# EEM_Connectors.net
KiCad netlist of a schematic drawn in Altium Designer
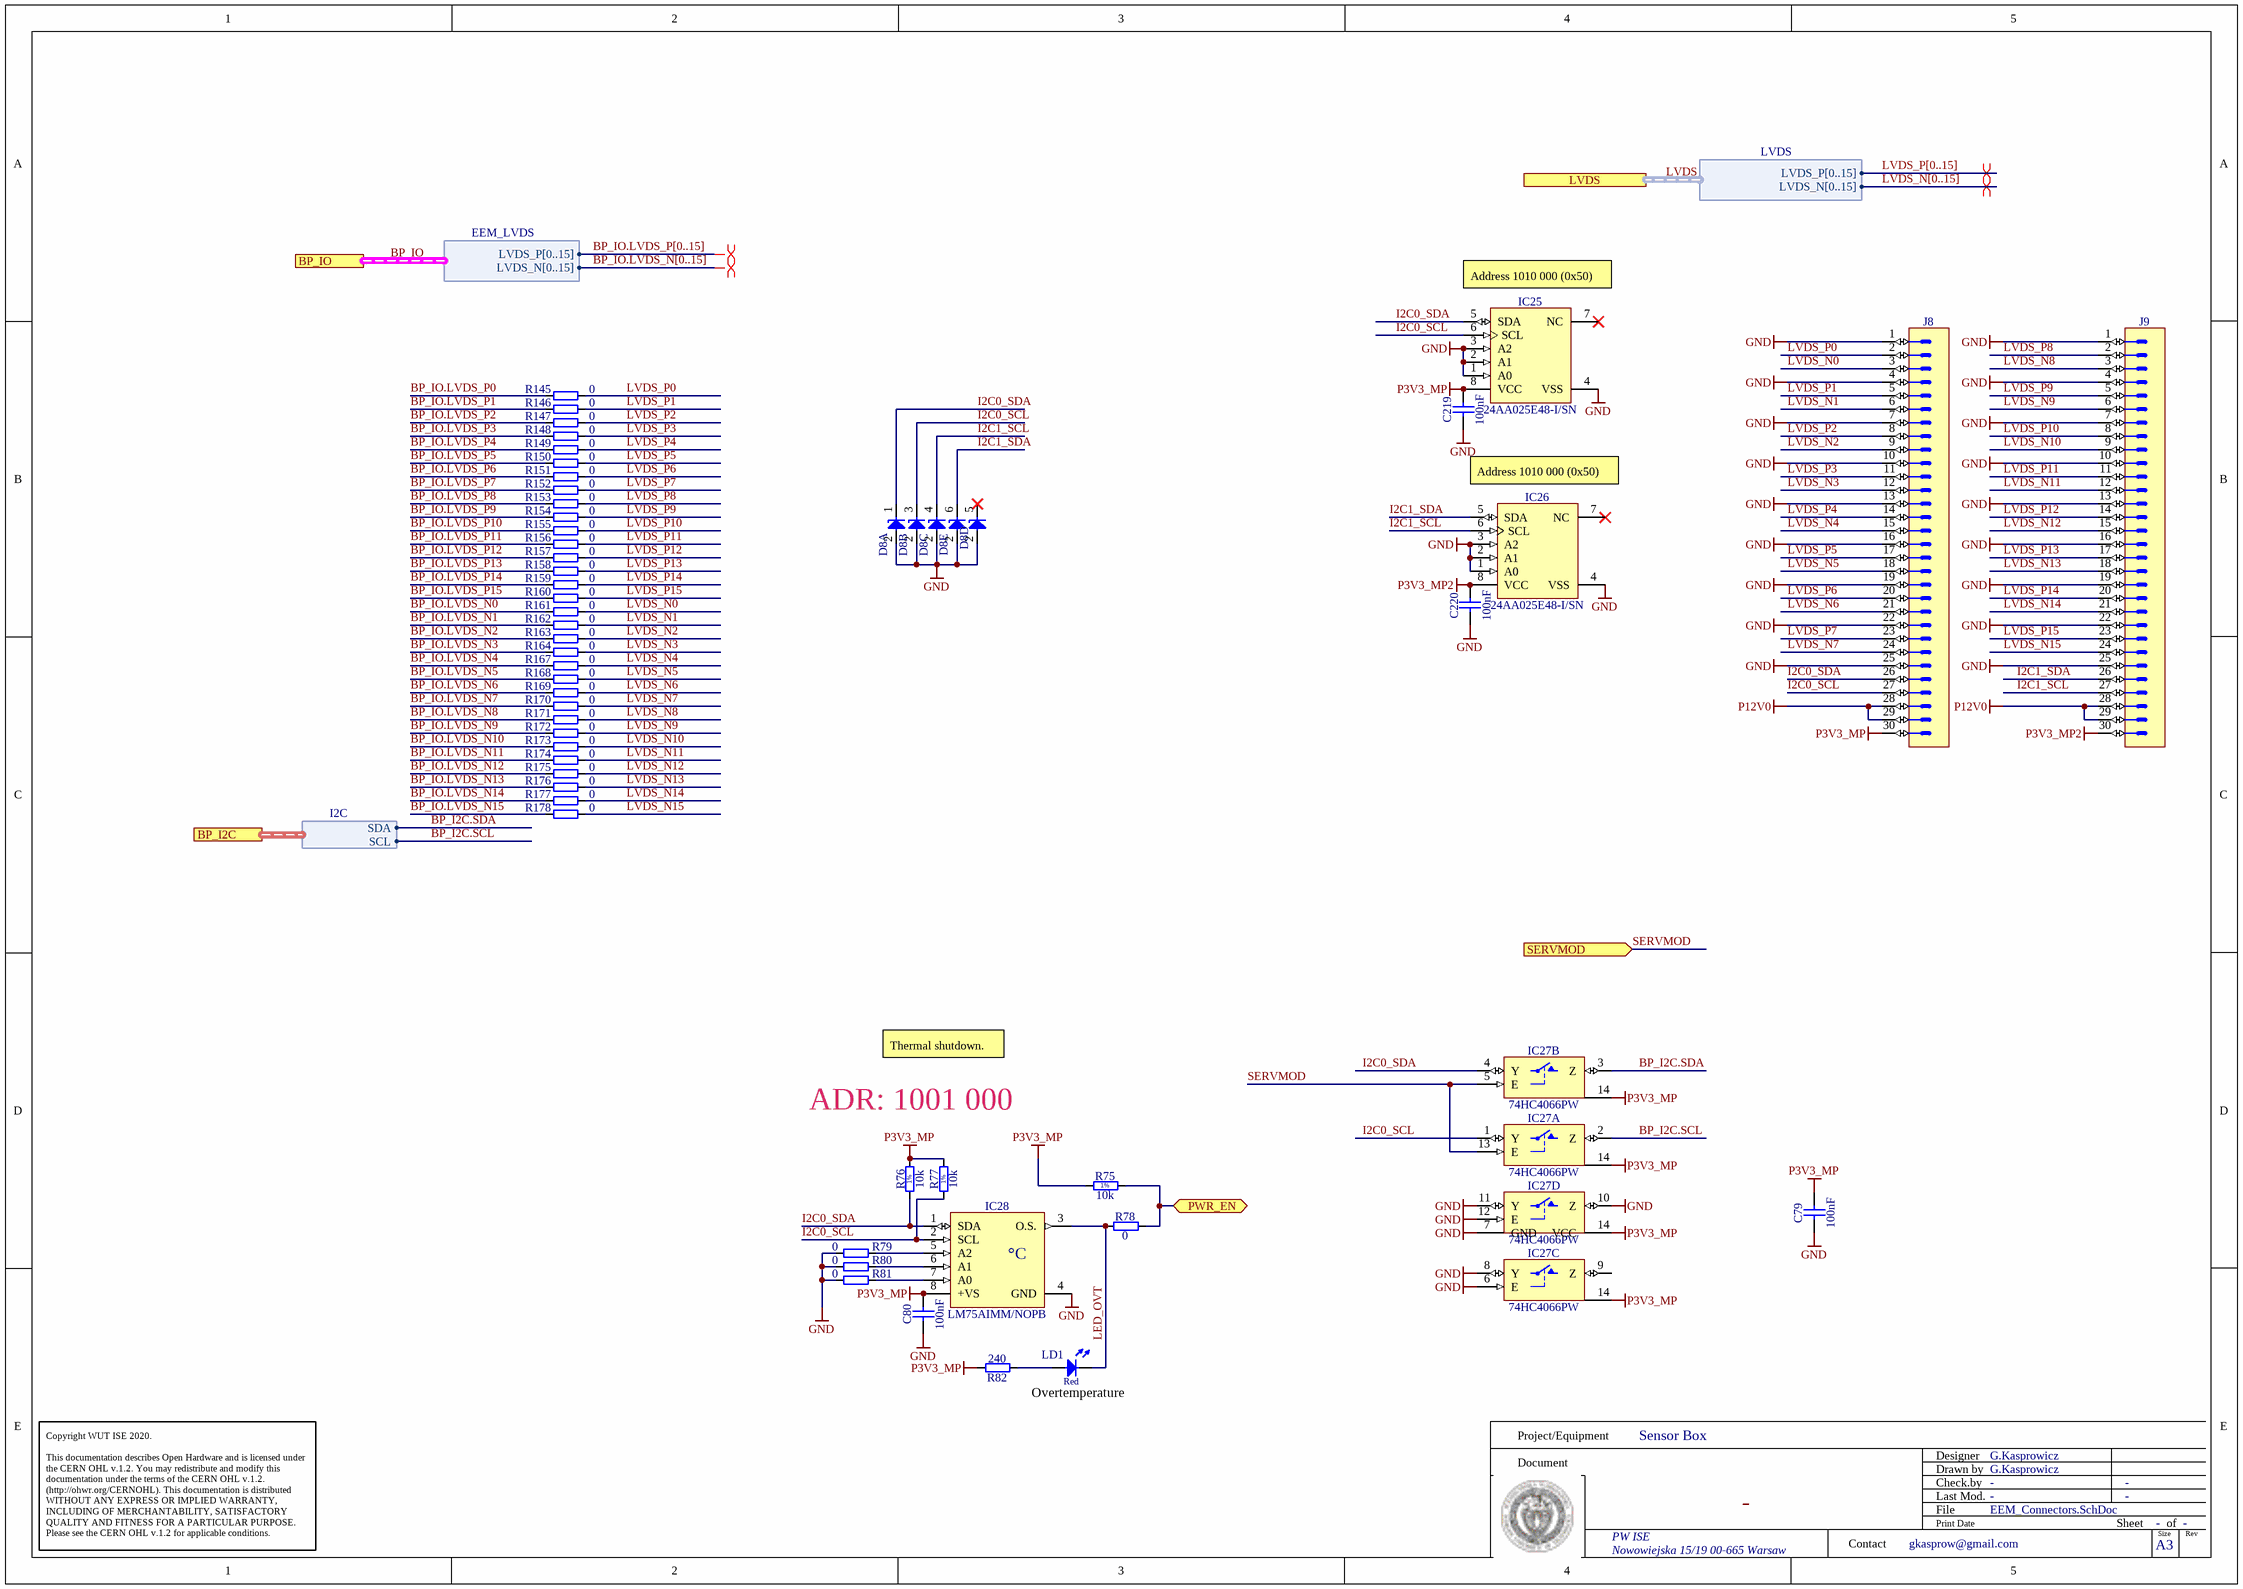
[diagram p0: EEM_Connectors.SchDoc]

(export (version "E")
  (design (tool "Eeschema 10.0.6"))
  (components
    (comp (ref "C79")
      (value "100nF")
      (footprint "CAPC1005X55N")
      (description "Non-polarised capacitor")
      (fields
        (field (name "PART NUMBER") "CC0402_100NF_16V_10%_X5R")
        (field (name "VOLTAGE") "16V")
        (field (name "AUTHOR") "CERN DEM JLC")
      )
      (libsource (lib "Capacitors") (part "Capacitor - non polarized"))
    )
    (comp (ref "C80")
      (value "100nF")
      (footprint "CAPC1005X55N")
      (description "Non-polarised capacitor")
      (fields
        (field (name "PART NUMBER") "CC0402_100NF_16V_10%_X5R")
        (field (name "VOLTAGE") "16V")
        (field (name "AUTHOR") "CERN DEM JLC")
      )
      (libsource (lib "Capacitors") (part "Capacitor - non polarized"))
    )
    (comp (ref "C219")
      (value "100nF")
      (footprint "CAPC1005X55N")
      (description "Non-polarised capacitor")
      (fields
        (field (name "PART NUMBER") "CC0402_100NF_16V_10%_X5R")
        (field (name "VOLTAGE") "16V")
        (field (name "AUTHOR") "CERN DEM JLC")
      )
      (libsource (lib "Capacitors") (part "Capacitor - non polarized"))
    )
    (comp (ref "C220")
      (value "100nF")
      (footprint "CAPC1005X55N")
      (description "Non-polarised capacitor")
      (fields
        (field (name "PART NUMBER") "CC0402_100NF_16V_10%_X5R")
        (field (name "VOLTAGE") "16V")
        (field (name "AUTHOR") "CERN DEM JLC")
      )
      (libsource (lib "Capacitors") (part "Capacitor - non polarized"))
    )
    (comp (ref "D8")
      (value "PESD3V3L5UY")
      (footprint "SOT65P210X110-6N")
      (description "Fivefold ESD Protection Diode Arrays")
      (fields
        (field (name "VOLTAGE") "3.3V")
        (field (name "POWER") "200W")
        (field (name "AUTHOR") "CERN DEM WB")
      )
      (libsource (lib "ICs And Semiconductors") (part "PESD Array 5diodes 6pins Common anode2"))
    )
    (comp (ref "IC25")
      (value "24AA025E48-I/SN")
      (footprint "SOIC127P600X175-8N")
      (description "1.7V-5.5V, 2K I2C™ Serial EEPROMs with EUI-48™ Node Identity")
      (fields (field (name "MANUFACTURER") "MICROCHIP TECHNOLOGY") (field (name "AUTHOR") "CERN DEM MR"))
      (libsource (lib "ICs And Semiconductors") (part "24AA025E48-I/SN"))
    )
    (comp (ref "IC26")
      (value "24AA025E48-I/SN")
      (footprint "SOIC127P600X175-8N")
      (description "1.7V-5.5V, 2K I2C™ Serial EEPROMs with EUI-48™ Node Identity")
      (fields (field (name "MANUFACTURER") "MICROCHIP TECHNOLOGY") (field (name "AUTHOR") "CERN DEM MR"))
      (libsource (lib "ICs And Semiconductors") (part "24AA025E48-I/SN"))
    )
    (comp (ref "IC27")
      (value "74HC4066PW")
      (footprint "SOP65P640X110-14N")
      (fields (field (name "MANUFACTURER") "NXP SEMICONDUCTORS") (field (name "AUTHOR") "CERN DEM JLC"))
      (libsource (lib "ICs And Semiconductors") (part "4066"))
    )
    (comp (ref "IC28")
      (value "LM75AIMM/NOPB")
      (footprint "SOP65P490X109-8N")
      (description "Digital Temperature Sensor and Thermal Watchdog with Two-Wire Interface")
      (fields (field (name "MANUFACTURER") "TEXAS INSTRUMENTS") (field (name "AUTHOR") "CERN DEM JLC"))
      (libsource (lib "ICs And Semiconductors") (part "LM75"))
    )
    (comp (ref "J8")
      (value "~")
      (footprint "3M_N2530-6002RB")
      (description "Connector 30 Male")
      (fields
        (field (name "PART NUMBER") "3M_N2530-6002RB")
        (field (name "MANUFACTURER") "3M")
        (field (name "AUTHOR") "CERN DEM JLC")
      )
      (libsource (lib "Connectors") (part "Connector 30 Male"))
    )
    (comp (ref "J9")
      (value "~")
      (footprint "3M_N2530-6002RB")
      (description "Connector 30 Male")
      (fields
        (field (name "PART NUMBER") "3M_N2530-6002RB")
        (field (name "MANUFACTURER") "3M")
        (field (name "AUTHOR") "CERN DEM JLC")
      )
      (libsource (lib "Connectors") (part "Connector 30 Male"))
    )
    (comp (ref "LD1")
      (value "Red")
      (footprint "LED_AVAGO_HSMC-C120")
      (description "LED Red 1C 2A")
      (fields
        (field (name "PART NUMBER") "LED_AVAGO_HSMC-C120")
        (field (name "MANUFACTURER") "AVAGO TECHNOLOGIES")
        (field (name "AUTHOR") "CERN DEM JMW")
      )
      (libsource (lib "ICs And Semiconductors") (part "LED Red 1C 2A"))
    )
    (comp (ref "R75")
      (value "10k")
      (footprint "RESC1005X40N")
      (description "Resistor - 1%")
      (fields
        (field (name "PART NUMBER") "R0402_10K_1%_0.0625W_100PPM")
        (field (name "POWER") "0.0625W")
        (field (name "AUTHOR") "CERN DEM JLC")
      )
      (libsource (lib "Resistors") (part "Resistor - 1%"))
    )
    (comp (ref "R76")
      (value "10k")
      (footprint "RESC1005X40N")
      (description "Resistor - 1%")
      (fields
        (field (name "PART NUMBER") "R0402_10K_1%_0.0625W_100PPM")
        (field (name "POWER") "0.0625W")
        (field (name "AUTHOR") "CERN DEM JLC")
      )
      (libsource (lib "Resistors") (part "Resistor - 1%"))
    )
    (comp (ref "R77")
      (value "10k")
      (footprint "RESC1005X40N")
      (description "Resistor - 1%")
      (fields
        (field (name "PART NUMBER") "R0402_10K_1%_0.0625W_100PPM")
        (field (name "POWER") "0.0625W")
        (field (name "AUTHOR") "CERN DEM JLC")
      )
      (libsource (lib "Resistors") (part "Resistor - 1%"))
    )
    (comp (ref "R78")
      (value "0")
      (footprint "RESC1005X40N")
      (description "Resistor")
      (fields
        (field (name "PART NUMBER") "R0402_0R_JUMPER")
        (field (name "MANUFACTURER") "GENERIC")
        (field (name "AUTHOR") "CERN DEM JLC")
      )
      (libsource (lib "Resistors") (part "Resistor"))
    )
    (comp (ref "R79")
      (value "0")
      (footprint "RESC1005X40N")
      (description "Resistor")
      (fields
        (field (name "PART NUMBER") "R0402_0R_JUMPER")
        (field (name "MANUFACTURER") "GENERIC")
        (field (name "AUTHOR") "CERN DEM JLC")
      )
      (libsource (lib "Resistors") (part "Resistor"))
    )
    (comp (ref "R80")
      (value "0")
      (footprint "RESC1005X40N")
      (description "Resistor")
      (fields
        (field (name "PART NUMBER") "R0402_0R_JUMPER")
        (field (name "MANUFACTURER") "GENERIC")
        (field (name "AUTHOR") "CERN DEM JLC")
      )
      (libsource (lib "Resistors") (part "Resistor"))
    )
    (comp (ref "R81")
      (value "0")
      (footprint "RESC1005X40N")
      (description "Resistor")
      (fields
        (field (name "PART NUMBER") "R0402_0R_JUMPER")
        (field (name "MANUFACTURER") "GENERIC")
        (field (name "AUTHOR") "CERN DEM JLC")
      )
      (libsource (lib "Resistors") (part "Resistor"))
    )
    (comp (ref "R82")
      (value "240")
      (footprint "RESC1005X40N")
      (description "Resistor - 1%")
      (fields
        (field (name "PART NUMBER") "R0402_240R_1%_0.0625W_100PPM")
        (field (name "POWER") "0.0625W")
        (field (name "AUTHOR") "CERN DEM JLC")
      )
      (libsource (lib "Resistors") (part "Resistor - 1%"))
    )
    (comp (ref "R145")
      (value "0")
      (footprint "RESC1005X40N")
      (description "Resistor")
      (fields
        (field (name "PART NUMBER") "R0402_0R_JUMPER")
        (field (name "MANUFACTURER") "GENERIC")
        (field (name "AUTHOR") "CERN DEM JLC")
      )
      (libsource (lib "Resistors") (part "Resistor"))
    )
    (comp (ref "R146")
      (value "0")
      (footprint "RESC1005X40N")
      (description "Resistor")
      (fields
        (field (name "PART NUMBER") "R0402_0R_JUMPER")
        (field (name "MANUFACTURER") "GENERIC")
        (field (name "AUTHOR") "CERN DEM JLC")
      )
      (libsource (lib "Resistors") (part "Resistor"))
    )
    (comp (ref "R147")
      (value "0")
      (footprint "RESC1005X40N")
      (description "Resistor")
      (fields
        (field (name "PART NUMBER") "R0402_0R_JUMPER")
        (field (name "MANUFACTURER") "GENERIC")
        (field (name "AUTHOR") "CERN DEM JLC")
      )
      (libsource (lib "Resistors") (part "Resistor"))
    )
    (comp (ref "R148")
      (value "0")
      (footprint "RESC1005X40N")
      (description "Resistor")
      (fields
        (field (name "PART NUMBER") "R0402_0R_JUMPER")
        (field (name "MANUFACTURER") "GENERIC")
        (field (name "AUTHOR") "CERN DEM JLC")
      )
      (libsource (lib "Resistors") (part "Resistor"))
    )
    (comp (ref "R149")
      (value "0")
      (footprint "RESC1005X40N")
      (description "Resistor")
      (fields
        (field (name "PART NUMBER") "R0402_0R_JUMPER")
        (field (name "MANUFACTURER") "GENERIC")
        (field (name "AUTHOR") "CERN DEM JLC")
      )
      (libsource (lib "Resistors") (part "Resistor"))
    )
    (comp (ref "R150")
      (value "0")
      (footprint "RESC1005X40N")
      (description "Resistor")
      (fields
        (field (name "PART NUMBER") "R0402_0R_JUMPER")
        (field (name "MANUFACTURER") "GENERIC")
        (field (name "AUTHOR") "CERN DEM JLC")
      )
      (libsource (lib "Resistors") (part "Resistor"))
    )
    (comp (ref "R151")
      (value "0")
      (footprint "RESC1005X40N")
      (description "Resistor")
      (fields
        (field (name "PART NUMBER") "R0402_0R_JUMPER")
        (field (name "MANUFACTURER") "GENERIC")
        (field (name "AUTHOR") "CERN DEM JLC")
      )
      (libsource (lib "Resistors") (part "Resistor"))
    )
    (comp (ref "R152")
      (value "0")
      (footprint "RESC1005X40N")
      (description "Resistor")
      (fields
        (field (name "PART NUMBER") "R0402_0R_JUMPER")
        (field (name "MANUFACTURER") "GENERIC")
        (field (name "AUTHOR") "CERN DEM JLC")
      )
      (libsource (lib "Resistors") (part "Resistor"))
    )
    (comp (ref "R153")
      (value "0")
      (footprint "RESC1005X40N")
      (description "Resistor")
      (fields
        (field (name "PART NUMBER") "R0402_0R_JUMPER")
        (field (name "MANUFACTURER") "GENERIC")
        (field (name "AUTHOR") "CERN DEM JLC")
      )
      (libsource (lib "Resistors") (part "Resistor"))
    )
    (comp (ref "R154")
      (value "0")
      (footprint "RESC1005X40N")
      (description "Resistor")
      (fields
        (field (name "PART NUMBER") "R0402_0R_JUMPER")
        (field (name "MANUFACTURER") "GENERIC")
        (field (name "AUTHOR") "CERN DEM JLC")
      )
      (libsource (lib "Resistors") (part "Resistor"))
    )
    (comp (ref "R155")
      (value "0")
      (footprint "RESC1005X40N")
      (description "Resistor")
      (fields
        (field (name "PART NUMBER") "R0402_0R_JUMPER")
        (field (name "MANUFACTURER") "GENERIC")
        (field (name "AUTHOR") "CERN DEM JLC")
      )
      (libsource (lib "Resistors") (part "Resistor"))
    )
    (comp (ref "R156")
      (value "0")
      (footprint "RESC1005X40N")
      (description "Resistor")
      (fields
        (field (name "PART NUMBER") "R0402_0R_JUMPER")
        (field (name "MANUFACTURER") "GENERIC")
        (field (name "AUTHOR") "CERN DEM JLC")
      )
      (libsource (lib "Resistors") (part "Resistor"))
    )
    (comp (ref "R157")
      (value "0")
      (footprint "RESC1005X40N")
      (description "Resistor")
      (fields
        (field (name "PART NUMBER") "R0402_0R_JUMPER")
        (field (name "MANUFACTURER") "GENERIC")
        (field (name "AUTHOR") "CERN DEM JLC")
      )
      (libsource (lib "Resistors") (part "Resistor"))
    )
    (comp (ref "R158")
      (value "0")
      (footprint "RESC1005X40N")
      (description "Resistor")
      (fields
        (field (name "PART NUMBER") "R0402_0R_JUMPER")
        (field (name "MANUFACTURER") "GENERIC")
        (field (name "AUTHOR") "CERN DEM JLC")
      )
      (libsource (lib "Resistors") (part "Resistor"))
    )
    (comp (ref "R159")
      (value "0")
      (footprint "RESC1005X40N")
      (description "Resistor")
      (fields
        (field (name "PART NUMBER") "R0402_0R_JUMPER")
        (field (name "MANUFACTURER") "GENERIC")
        (field (name "AUTHOR") "CERN DEM JLC")
      )
      (libsource (lib "Resistors") (part "Resistor"))
    )
    (comp (ref "R160")
      (value "0")
      (footprint "RESC1005X40N")
      (description "Resistor")
      (fields
        (field (name "PART NUMBER") "R0402_0R_JUMPER")
        (field (name "MANUFACTURER") "GENERIC")
        (field (name "AUTHOR") "CERN DEM JLC")
      )
      (libsource (lib "Resistors") (part "Resistor"))
    )
    (comp (ref "R161")
      (value "0")
      (footprint "RESC1005X40N")
      (description "Resistor")
      (fields
        (field (name "PART NUMBER") "R0402_0R_JUMPER")
        (field (name "MANUFACTURER") "GENERIC")
        (field (name "AUTHOR") "CERN DEM JLC")
      )
      (libsource (lib "Resistors") (part "Resistor"))
    )
    (comp (ref "R162")
      (value "0")
      (footprint "RESC1005X40N")
      (description "Resistor")
      (fields
        (field (name "PART NUMBER") "R0402_0R_JUMPER")
        (field (name "MANUFACTURER") "GENERIC")
        (field (name "AUTHOR") "CERN DEM JLC")
      )
      (libsource (lib "Resistors") (part "Resistor"))
    )
    (comp (ref "R163")
      (value "0")
      (footprint "RESC1005X40N")
      (description "Resistor")
      (fields
        (field (name "PART NUMBER") "R0402_0R_JUMPER")
        (field (name "MANUFACTURER") "GENERIC")
        (field (name "AUTHOR") "CERN DEM JLC")
      )
      (libsource (lib "Resistors") (part "Resistor"))
    )
    (comp (ref "R164")
      (value "0")
      (footprint "RESC1005X40N")
      (description "Resistor")
      (fields
        (field (name "PART NUMBER") "R0402_0R_JUMPER")
        (field (name "MANUFACTURER") "GENERIC")
        (field (name "AUTHOR") "CERN DEM JLC")
      )
      (libsource (lib "Resistors") (part "Resistor"))
    )
    (comp (ref "R167")
      (value "0")
      (footprint "RESC1005X40N")
      (description "Resistor")
      (fields
        (field (name "PART NUMBER") "R0402_0R_JUMPER")
        (field (name "MANUFACTURER") "GENERIC")
        (field (name "AUTHOR") "CERN DEM JLC")
      )
      (libsource (lib "Resistors") (part "Resistor"))
    )
    (comp (ref "R168")
      (value "0")
      (footprint "RESC1005X40N")
      (description "Resistor")
      (fields
        (field (name "PART NUMBER") "R0402_0R_JUMPER")
        (field (name "MANUFACTURER") "GENERIC")
        (field (name "AUTHOR") "CERN DEM JLC")
      )
      (libsource (lib "Resistors") (part "Resistor"))
    )
    (comp (ref "R169")
      (value "0")
      (footprint "RESC1005X40N")
      (description "Resistor")
      (fields
        (field (name "PART NUMBER") "R0402_0R_JUMPER")
        (field (name "MANUFACTURER") "GENERIC")
        (field (name "AUTHOR") "CERN DEM JLC")
      )
      (libsource (lib "Resistors") (part "Resistor"))
    )
    (comp (ref "R170")
      (value "0")
      (footprint "RESC1005X40N")
      (description "Resistor")
      (fields
        (field (name "PART NUMBER") "R0402_0R_JUMPER")
        (field (name "MANUFACTURER") "GENERIC")
        (field (name "AUTHOR") "CERN DEM JLC")
      )
      (libsource (lib "Resistors") (part "Resistor"))
    )
    (comp (ref "R171")
      (value "0")
      (footprint "RESC1005X40N")
      (description "Resistor")
      (fields
        (field (name "PART NUMBER") "R0402_0R_JUMPER")
        (field (name "MANUFACTURER") "GENERIC")
        (field (name "AUTHOR") "CERN DEM JLC")
      )
      (libsource (lib "Resistors") (part "Resistor"))
    )
    (comp (ref "R172")
      (value "0")
      (footprint "RESC1005X40N")
      (description "Resistor")
      (fields
        (field (name "PART NUMBER") "R0402_0R_JUMPER")
        (field (name "MANUFACTURER") "GENERIC")
        (field (name "AUTHOR") "CERN DEM JLC")
      )
      (libsource (lib "Resistors") (part "Resistor"))
    )
    (comp (ref "R173")
      (value "0")
      (footprint "RESC1005X40N")
      (description "Resistor")
      (fields
        (field (name "PART NUMBER") "R0402_0R_JUMPER")
        (field (name "MANUFACTURER") "GENERIC")
        (field (name "AUTHOR") "CERN DEM JLC")
      )
      (libsource (lib "Resistors") (part "Resistor"))
    )
    (comp (ref "R174")
      (value "0")
      (footprint "RESC1005X40N")
      (description "Resistor")
      (fields
        (field (name "PART NUMBER") "R0402_0R_JUMPER")
        (field (name "MANUFACTURER") "GENERIC")
        (field (name "AUTHOR") "CERN DEM JLC")
      )
      (libsource (lib "Resistors") (part "Resistor"))
    )
    (comp (ref "R175")
      (value "0")
      (footprint "RESC1005X40N")
      (description "Resistor")
      (fields
        (field (name "PART NUMBER") "R0402_0R_JUMPER")
        (field (name "MANUFACTURER") "GENERIC")
        (field (name "AUTHOR") "CERN DEM JLC")
      )
      (libsource (lib "Resistors") (part "Resistor"))
    )
    (comp (ref "R176")
      (value "0")
      (footprint "RESC1005X40N")
      (description "Resistor")
      (fields
        (field (name "PART NUMBER") "R0402_0R_JUMPER")
        (field (name "MANUFACTURER") "GENERIC")
        (field (name "AUTHOR") "CERN DEM JLC")
      )
      (libsource (lib "Resistors") (part "Resistor"))
    )
    (comp (ref "R177")
      (value "0")
      (footprint "RESC1005X40N")
      (description "Resistor")
      (fields
        (field (name "PART NUMBER") "R0402_0R_JUMPER")
        (field (name "MANUFACTURER") "GENERIC")
        (field (name "AUTHOR") "CERN DEM JLC")
      )
      (libsource (lib "Resistors") (part "Resistor"))
    )
    (comp (ref "R178")
      (value "0")
      (footprint "RESC1005X40N")
      (description "Resistor")
      (fields
        (field (name "PART NUMBER") "R0402_0R_JUMPER")
        (field (name "MANUFACTURER") "GENERIC")
        (field (name "AUTHOR") "CERN DEM JLC")
      )
      (libsource (lib "Resistors") (part "Resistor"))
    )
  )
  (nets
    (net (code "4") (name "/BP_I2C.SCL") (class "Default")
      (node (ref "IC27") (pin "2") (pinfunction "Z_2") (pintype "bidirectional"))
    )
    (net (code "5") (name "/BP_I2C.SDA") (class "Default")
      (node (ref "IC27") (pin "3") (pinfunction "Z_3") (pintype "bidirectional"))
    )
    (net (code "6") (name "/BP_IO.LVDS_N0") (class "Default")
      (node (ref "R161") (pin "1") (pinfunction "1_1") (pintype "passive"))
    )
    (net (code "7") (name "/BP_IO.LVDS_N1") (class "Default")
      (node (ref "R162") (pin "1") (pinfunction "1_1") (pintype "passive"))
    )
    (net (code "8") (name "/BP_IO.LVDS_N2") (class "Default")
      (node (ref "R163") (pin "1") (pinfunction "1_1") (pintype "passive"))
    )
    (net (code "9") (name "/BP_IO.LVDS_N3") (class "Default")
      (node (ref "R164") (pin "1") (pinfunction "1_1") (pintype "passive"))
    )
    (net (code "10") (name "/BP_IO.LVDS_N4") (class "Default")
      (node (ref "R167") (pin "1") (pinfunction "1_1") (pintype "passive"))
    )
    (net (code "11") (name "/BP_IO.LVDS_N5") (class "Default")
      (node (ref "R168") (pin "1") (pinfunction "1_1") (pintype "passive"))
    )
    (net (code "12") (name "/BP_IO.LVDS_N6") (class "Default")
      (node (ref "R169") (pin "1") (pinfunction "1_1") (pintype "passive"))
    )
    (net (code "13") (name "/BP_IO.LVDS_N7") (class "Default")
      (node (ref "R170") (pin "1") (pinfunction "1_1") (pintype "passive"))
    )
    (net (code "14") (name "/BP_IO.LVDS_N8") (class "Default")
      (node (ref "R171") (pin "1") (pinfunction "1_1") (pintype "passive"))
    )
    (net (code "15") (name "/BP_IO.LVDS_N9") (class "Default")
      (node (ref "R172") (pin "1") (pinfunction "1_1") (pintype "passive"))
    )
    (net (code "16") (name "/BP_IO.LVDS_N10") (class "Default")
      (node (ref "R173") (pin "1") (pinfunction "1_1") (pintype "passive"))
    )
    (net (code "17") (name "/BP_IO.LVDS_N11") (class "Default")
      (node (ref "R174") (pin "1") (pinfunction "1_1") (pintype "passive"))
    )
    (net (code "18") (name "/BP_IO.LVDS_N12") (class "Default")
      (node (ref "R175") (pin "1") (pinfunction "1_1") (pintype "passive"))
    )
    (net (code "19") (name "/BP_IO.LVDS_N13") (class "Default")
      (node (ref "R176") (pin "1") (pinfunction "1_1") (pintype "passive"))
    )
    (net (code "20") (name "/BP_IO.LVDS_N14") (class "Default")
      (node (ref "R177") (pin "1") (pinfunction "1_1") (pintype "passive"))
    )
    (net (code "21") (name "/BP_IO.LVDS_N15") (class "Default")
      (node (ref "R178") (pin "1") (pinfunction "1_1") (pintype "passive"))
    )
    (net (code "23") (name "/BP_IO.LVDS_P0") (class "Default")
      (node (ref "R145") (pin "1") (pinfunction "1_1") (pintype "passive"))
    )
    (net (code "24") (name "/BP_IO.LVDS_P1") (class "Default")
      (node (ref "R146") (pin "1") (pinfunction "1_1") (pintype "passive"))
    )
    (net (code "25") (name "/BP_IO.LVDS_P2") (class "Default")
      (node (ref "R147") (pin "1") (pinfunction "1_1") (pintype "passive"))
    )
    (net (code "26") (name "/BP_IO.LVDS_P3") (class "Default")
      (node (ref "R148") (pin "1") (pinfunction "1_1") (pintype "passive"))
    )
    (net (code "27") (name "/BP_IO.LVDS_P4") (class "Default")
      (node (ref "R149") (pin "1") (pinfunction "1_1") (pintype "passive"))
    )
    (net (code "28") (name "/BP_IO.LVDS_P5") (class "Default")
      (node (ref "R150") (pin "1") (pinfunction "1_1") (pintype "passive"))
    )
    (net (code "29") (name "/BP_IO.LVDS_P6") (class "Default")
      (node (ref "R151") (pin "1") (pinfunction "1_1") (pintype "passive"))
    )
    (net (code "30") (name "/BP_IO.LVDS_P7") (class "Default")
      (node (ref "R152") (pin "1") (pinfunction "1_1") (pintype "passive"))
    )
    (net (code "31") (name "/BP_IO.LVDS_P8") (class "Default")
      (node (ref "R153") (pin "1") (pinfunction "1_1") (pintype "passive"))
    )
    (net (code "32") (name "/BP_IO.LVDS_P9") (class "Default")
      (node (ref "R154") (pin "1") (pinfunction "1_1") (pintype "passive"))
    )
    (net (code "33") (name "/BP_IO.LVDS_P10") (class "Default")
      (node (ref "R155") (pin "1") (pinfunction "1_1") (pintype "passive"))
    )
    (net (code "34") (name "/BP_IO.LVDS_P11") (class "Default")
      (node (ref "R156") (pin "1") (pinfunction "1_1") (pintype "passive"))
    )
    (net (code "35") (name "/BP_IO.LVDS_P12") (class "Default")
      (node (ref "R157") (pin "1") (pinfunction "1_1") (pintype "passive"))
    )
    (net (code "36") (name "/BP_IO.LVDS_P13") (class "Default")
      (node (ref "R158") (pin "1") (pinfunction "1_1") (pintype "passive"))
    )
    (net (code "37") (name "/BP_IO.LVDS_P14") (class "Default")
      (node (ref "R159") (pin "1") (pinfunction "1_1") (pintype "passive"))
    )
    (net (code "38") (name "/BP_IO.LVDS_P15") (class "Default")
      (node (ref "R160") (pin "1") (pinfunction "1_1") (pintype "passive"))
    )
    (net (code "41") (name "/I2C0_SCL") (class "Default")
      (node (ref "D8") (pin "3") (pinfunction "C_3") (pintype "passive"))
      (node (ref "IC25") (pin "6") (pinfunction "SCL_6") (pintype "input"))
      (node (ref "IC27") (pin "1") (pinfunction "Y_1") (pintype "bidirectional"))
      (node (ref "IC28") (pin "2") (pinfunction "SCL_2") (pintype "input"))
      (node (ref "J8") (pin "27") (pinfunction "27_27") (pintype "bidirectional"))
      (node (ref "R77") (pin "1") (pinfunction "1_1") (pintype "passive"))
    )
    (net (code "42") (name "/I2C0_SDA") (class "Default")
      (node (ref "D8") (pin "1") (pinfunction "C_1") (pintype "passive"))
      (node (ref "IC25") (pin "5") (pinfunction "SDA_5") (pintype "bidirectional"))
      (node (ref "IC27") (pin "4") (pinfunction "Y_4") (pintype "bidirectional"))
      (node (ref "IC28") (pin "1") (pinfunction "SDA_1") (pintype "bidirectional"))
      (node (ref "J8") (pin "26") (pinfunction "26_26") (pintype "bidirectional"))
      (node (ref "R76") (pin "1") (pinfunction "1_1") (pintype "passive"))
    )
    (net (code "43") (name "/I2C1_SCL") (class "Default")
      (node (ref "D8") (pin "4") (pinfunction "C_4") (pintype "passive"))
      (node (ref "IC26") (pin "6") (pinfunction "SCL_6") (pintype "input"))
      (node (ref "J9") (pin "27") (pinfunction "27_27") (pintype "bidirectional"))
    )
    (net (code "44") (name "/I2C1_SDA") (class "Default")
      (node (ref "D8") (pin "6") (pinfunction "C_6") (pintype "passive"))
      (node (ref "IC26") (pin "5") (pinfunction "SDA_5") (pintype "bidirectional"))
      (node (ref "J9") (pin "26") (pinfunction "26_26") (pintype "bidirectional"))
    )
    (net (code "45") (name "/LED_OVT") (class "Default")
      (node (ref "IC28") (pin "3") (pinfunction "O.S._3") (pintype "output"))
      (node (ref "LD1") (pin "1") (pinfunction "C_1") (pintype "passive"))
      (node (ref "R78") (pin "1") (pinfunction "1_1") (pintype "passive"))
    )
    (net (code "46") (name "/LVDS_N0") (class "Default")
      (node (ref "J8") (pin "3") (pinfunction "3_3") (pintype "bidirectional"))
      (node (ref "R161") (pin "2") (pinfunction "2_2") (pintype "passive"))
    )
    (net (code "47") (name "/LVDS_N1") (class "Default")
      (node (ref "J8") (pin "6") (pinfunction "6_6") (pintype "bidirectional"))
      (node (ref "R162") (pin "2") (pinfunction "2_2") (pintype "passive"))
    )
    (net (code "48") (name "/LVDS_N2") (class "Default")
      (node (ref "J8") (pin "9") (pinfunction "9_9") (pintype "bidirectional"))
      (node (ref "R163") (pin "2") (pinfunction "2_2") (pintype "passive"))
    )
    (net (code "49") (name "/LVDS_N3") (class "Default")
      (node (ref "J8") (pin "12") (pinfunction "12_12") (pintype "bidirectional"))
      (node (ref "R164") (pin "2") (pinfunction "2_2") (pintype "passive"))
    )
    (net (code "50") (name "/LVDS_N4") (class "Default")
      (node (ref "J8") (pin "15") (pinfunction "15_15") (pintype "bidirectional"))
      (node (ref "R167") (pin "2") (pinfunction "2_2") (pintype "passive"))
    )
    (net (code "51") (name "/LVDS_N5") (class "Default")
      (node (ref "J8") (pin "18") (pinfunction "18_18") (pintype "bidirectional"))
      (node (ref "R168") (pin "2") (pinfunction "2_2") (pintype "passive"))
    )
    (net (code "52") (name "/LVDS_N6") (class "Default")
      (node (ref "J8") (pin "21") (pinfunction "21_21") (pintype "bidirectional"))
      (node (ref "R169") (pin "2") (pinfunction "2_2") (pintype "passive"))
    )
    (net (code "53") (name "/LVDS_N7") (class "Default")
      (node (ref "J8") (pin "24") (pinfunction "24_24") (pintype "bidirectional"))
      (node (ref "R170") (pin "2") (pinfunction "2_2") (pintype "passive"))
    )
    (net (code "54") (name "/LVDS_N8") (class "Default")
      (node (ref "J9") (pin "3") (pinfunction "3_3") (pintype "bidirectional"))
      (node (ref "R171") (pin "2") (pinfunction "2_2") (pintype "passive"))
    )
    (net (code "55") (name "/LVDS_N9") (class "Default")
      (node (ref "J9") (pin "6") (pinfunction "6_6") (pintype "bidirectional"))
      (node (ref "R172") (pin "2") (pinfunction "2_2") (pintype "passive"))
    )
    (net (code "56") (name "/LVDS_N10") (class "Default")
      (node (ref "J9") (pin "9") (pinfunction "9_9") (pintype "bidirectional"))
      (node (ref "R173") (pin "2") (pinfunction "2_2") (pintype "passive"))
    )
    (net (code "57") (name "/LVDS_N11") (class "Default")
      (node (ref "J9") (pin "12") (pinfunction "12_12") (pintype "bidirectional"))
      (node (ref "R174") (pin "2") (pinfunction "2_2") (pintype "passive"))
    )
    (net (code "58") (name "/LVDS_N12") (class "Default")
      (node (ref "J9") (pin "15") (pinfunction "15_15") (pintype "bidirectional"))
      (node (ref "R175") (pin "2") (pinfunction "2_2") (pintype "passive"))
    )
    (net (code "59") (name "/LVDS_N13") (class "Default")
      (node (ref "J9") (pin "18") (pinfunction "18_18") (pintype "bidirectional"))
      (node (ref "R176") (pin "2") (pinfunction "2_2") (pintype "passive"))
    )
    (net (code "60") (name "/LVDS_N14") (class "Default")
      (node (ref "J9") (pin "21") (pinfunction "21_21") (pintype "bidirectional"))
      (node (ref "R177") (pin "2") (pinfunction "2_2") (pintype "passive"))
    )
    (net (code "61") (name "/LVDS_N15") (class "Default")
      (node (ref "J9") (pin "24") (pinfunction "24_24") (pintype "bidirectional"))
      (node (ref "R178") (pin "2") (pinfunction "2_2") (pintype "passive"))
    )
    (net (code "62") (name "/LVDS_P0") (class "Default")
      (node (ref "J8") (pin "2") (pinfunction "2_2") (pintype "bidirectional"))
      (node (ref "R145") (pin "2") (pinfunction "2_2") (pintype "passive"))
    )
    (net (code "63") (name "/LVDS_P1") (class "Default")
      (node (ref "J8") (pin "5") (pinfunction "5_5") (pintype "bidirectional"))
      (node (ref "R146") (pin "2") (pinfunction "2_2") (pintype "passive"))
    )
    (net (code "64") (name "/LVDS_P2") (class "Default")
      (node (ref "J8") (pin "8") (pinfunction "8_8") (pintype "bidirectional"))
      (node (ref "R147") (pin "2") (pinfunction "2_2") (pintype "passive"))
    )
    (net (code "65") (name "/LVDS_P3") (class "Default")
      (node (ref "J8") (pin "11") (pinfunction "11_11") (pintype "bidirectional"))
      (node (ref "R148") (pin "2") (pinfunction "2_2") (pintype "passive"))
    )
    (net (code "66") (name "/LVDS_P4") (class "Default")
      (node (ref "J8") (pin "14") (pinfunction "14_14") (pintype "bidirectional"))
      (node (ref "R149") (pin "2") (pinfunction "2_2") (pintype "passive"))
    )
    (net (code "67") (name "/LVDS_P5") (class "Default")
      (node (ref "J8") (pin "17") (pinfunction "17_17") (pintype "bidirectional"))
      (node (ref "R150") (pin "2") (pinfunction "2_2") (pintype "passive"))
    )
    (net (code "68") (name "/LVDS_P6") (class "Default")
      (node (ref "J8") (pin "20") (pinfunction "20_20") (pintype "bidirectional"))
      (node (ref "R151") (pin "2") (pinfunction "2_2") (pintype "passive"))
    )
    (net (code "69") (name "/LVDS_P7") (class "Default")
      (node (ref "J8") (pin "23") (pinfunction "23_23") (pintype "bidirectional"))
      (node (ref "R152") (pin "2") (pinfunction "2_2") (pintype "passive"))
    )
    (net (code "70") (name "/LVDS_P8") (class "Default")
      (node (ref "J9") (pin "2") (pinfunction "2_2") (pintype "bidirectional"))
      (node (ref "R153") (pin "2") (pinfunction "2_2") (pintype "passive"))
    )
    (net (code "71") (name "/LVDS_P9") (class "Default")
      (node (ref "J9") (pin "5") (pinfunction "5_5") (pintype "bidirectional"))
      (node (ref "R154") (pin "2") (pinfunction "2_2") (pintype "passive"))
    )
    (net (code "72") (name "/LVDS_P10") (class "Default")
      (node (ref "J9") (pin "8") (pinfunction "8_8") (pintype "bidirectional"))
      (node (ref "R155") (pin "2") (pinfunction "2_2") (pintype "passive"))
    )
    (net (code "73") (name "/LVDS_P11") (class "Default")
      (node (ref "J9") (pin "11") (pinfunction "11_11") (pintype "bidirectional"))
      (node (ref "R156") (pin "2") (pinfunction "2_2") (pintype "passive"))
    )
    (net (code "74") (name "/LVDS_P12") (class "Default")
      (node (ref "J9") (pin "14") (pinfunction "14_14") (pintype "bidirectional"))
      (node (ref "R157") (pin "2") (pinfunction "2_2") (pintype "passive"))
    )
    (net (code "75") (name "/LVDS_P13") (class "Default")
      (node (ref "J9") (pin "17") (pinfunction "17_17") (pintype "bidirectional"))
      (node (ref "R158") (pin "2") (pinfunction "2_2") (pintype "passive"))
    )
    (net (code "76") (name "/LVDS_P14") (class "Default")
      (node (ref "J9") (pin "20") (pinfunction "20_20") (pintype "bidirectional"))
      (node (ref "R159") (pin "2") (pinfunction "2_2") (pintype "passive"))
    )
    (net (code "77") (name "/LVDS_P15") (class "Default")
      (node (ref "J9") (pin "23") (pinfunction "23_23") (pintype "bidirectional"))
      (node (ref "R160") (pin "2") (pinfunction "2_2") (pintype "passive"))
    )
    (net (code "79") (name "/PWR_EN") (class "Default")
      (node (ref "R75") (pin "2") (pinfunction "2_2") (pintype "passive"))
      (node (ref "R78") (pin "2") (pinfunction "2_2") (pintype "passive"))
    )
    (net (code "80") (name "/SERVMOD") (class "Default")
      (node (ref "IC27") (pin "13") (pinfunction "E_13") (pintype "input"))
      (node (ref "IC27") (pin "5") (pinfunction "E_5") (pintype "input"))
    )
    (net (code "83") (name "GND") (class "Default")
      (node (ref "C219") (pin "1") (pinfunction "1_1") (pintype "passive"))
      (node (ref "C220") (pin "1") (pinfunction "1_1") (pintype "passive"))
      (node (ref "C79") (pin "1") (pinfunction "1_1") (pintype "passive"))
      (node (ref "C80") (pin "1") (pinfunction "1_1") (pintype "passive"))
      (node (ref "D8") (pin "2") (pinfunction "A_2") (pintype "passive"))
      (node (ref "IC25") (pin "1") (pinfunction "A0_1") (pintype "input"))
      (node (ref "IC25") (pin "2") (pinfunction "A1_2") (pintype "input"))
      (node (ref "IC25") (pin "3") (pinfunction "A2_3") (pintype "input"))
      (node (ref "IC25") (pin "4") (pinfunction "VSS_4") (pintype "power_in"))
      (node (ref "IC26") (pin "1") (pinfunction "A0_1") (pintype "input"))
      (node (ref "IC26") (pin "2") (pinfunction "A1_2") (pintype "input"))
      (node (ref "IC26") (pin "3") (pinfunction "A2_3") (pintype "input"))
      (node (ref "IC26") (pin "4") (pinfunction "VSS_4") (pintype "power_in"))
      (node (ref "IC27") (pin "10") (pinfunction "Z_10") (pintype "bidirectional"))
      (node (ref "IC27") (pin "11") (pinfunction "Y_11") (pintype "bidirectional"))
      (node (ref "IC27") (pin "12") (pinfunction "E_12") (pintype "input"))
      (node (ref "IC27") (pin "6") (pinfunction "E_6") (pintype "input"))
      (node (ref "IC27") (pin "7") (pinfunction "GND_7") (pintype "power_in"))
      (node (ref "IC27") (pin "8") (pinfunction "Y_8") (pintype "bidirectional"))
      (node (ref "IC28") (pin "4") (pinfunction "GND_4") (pintype "power_in"))
      (node (ref "J8") (pin "1") (pinfunction "1_1") (pintype "bidirectional"))
      (node (ref "J8") (pin "10") (pinfunction "10_10") (pintype "bidirectional"))
      (node (ref "J8") (pin "13") (pinfunction "13_13") (pintype "bidirectional"))
      (node (ref "J8") (pin "16") (pinfunction "16_16") (pintype "bidirectional"))
      (node (ref "J8") (pin "19") (pinfunction "19_19") (pintype "bidirectional"))
      (node (ref "J8") (pin "22") (pinfunction "22_22") (pintype "bidirectional"))
      (node (ref "J8") (pin "25") (pinfunction "25_25") (pintype "bidirectional"))
      (node (ref "J8") (pin "4") (pinfunction "4_4") (pintype "bidirectional"))
      (node (ref "J8") (pin "7") (pinfunction "7_7") (pintype "bidirectional"))
      (node (ref "J9") (pin "1") (pinfunction "1_1") (pintype "bidirectional"))
      (node (ref "J9") (pin "10") (pinfunction "10_10") (pintype "bidirectional"))
      (node (ref "J9") (pin "13") (pinfunction "13_13") (pintype "bidirectional"))
      (node (ref "J9") (pin "16") (pinfunction "16_16") (pintype "bidirectional"))
      (node (ref "J9") (pin "19") (pinfunction "19_19") (pintype "bidirectional"))
      (node (ref "J9") (pin "22") (pinfunction "22_22") (pintype "bidirectional"))
      (node (ref "J9") (pin "25") (pinfunction "25_25") (pintype "bidirectional"))
      (node (ref "J9") (pin "4") (pinfunction "4_4") (pintype "bidirectional"))
      (node (ref "J9") (pin "7") (pinfunction "7_7") (pintype "bidirectional"))
      (node (ref "R79") (pin "1") (pinfunction "1_1") (pintype "passive"))
      (node (ref "R80") (pin "1") (pinfunction "1_1") (pintype "passive"))
      (node (ref "R81") (pin "1") (pinfunction "1_1") (pintype "passive"))
    )
    (net (code "84") (name "Net-(IC28-A0)") (class "Default")
      (node (ref "IC28") (pin "7") (pinfunction "A0_7") (pintype "input"))
      (node (ref "R81") (pin "2") (pinfunction "2_2") (pintype "passive"))
    )
    (net (code "85") (name "Net-(IC28-A1)") (class "Default")
      (node (ref "IC28") (pin "6") (pinfunction "A1_6") (pintype "input"))
      (node (ref "R80") (pin "2") (pinfunction "2_2") (pintype "passive"))
    )
    (net (code "86") (name "Net-(IC28-A2)") (class "Default")
      (node (ref "IC28") (pin "5") (pinfunction "A2_5") (pintype "input"))
      (node (ref "R79") (pin "2") (pinfunction "2_2") (pintype "passive"))
    )
    (net (code "87") (name "Net-(LD1-A)") (class "Default")
      (node (ref "LD1") (pin "2") (pinfunction "A_2") (pintype "passive"))
      (node (ref "R82") (pin "1") (pinfunction "1_1") (pintype "passive"))
    )
    (net (code "88") (name "P3V3_MP") (class "Default")
      (node (ref "C219") (pin "2") (pinfunction "2_2") (pintype "passive"))
      (node (ref "C79") (pin "2") (pinfunction "2_2") (pintype "passive"))
      (node (ref "C80") (pin "2") (pinfunction "2_2") (pintype "passive"))
      (node (ref "IC25") (pin "8") (pinfunction "VCC_8") (pintype "power_in"))
      (node (ref "IC27") (pin "14") (pinfunction "VCC_14") (pintype "power_in"))
      (node (ref "IC28") (pin "8") (pinfunction "+VS_8") (pintype "power_in"))
      (node (ref "J8") (pin "30") (pinfunction "30_30") (pintype "bidirectional"))
      (node (ref "R75") (pin "1") (pinfunction "1_1") (pintype "passive"))
      (node (ref "R76") (pin "2") (pinfunction "2_2") (pintype "passive"))
      (node (ref "R77") (pin "2") (pinfunction "2_2") (pintype "passive"))
      (node (ref "R82") (pin "2") (pinfunction "2_2") (pintype "passive"))
    )
    (net (code "89") (name "P3V3_MP2") (class "Default")
      (node (ref "C220") (pin "2") (pinfunction "2_2") (pintype "passive"))
      (node (ref "IC26") (pin "8") (pinfunction "VCC_8") (pintype "power_in"))
      (node (ref "J9") (pin "30") (pinfunction "30_30") (pintype "bidirectional"))
    )
    (net (code "90") (name "P12V0") (class "Default")
      (node (ref "J8") (pin "28") (pinfunction "28_28") (pintype "bidirectional"))
      (node (ref "J8") (pin "29") (pinfunction "29_29") (pintype "bidirectional"))
      (node (ref "J9") (pin "28") (pinfunction "28_28") (pintype "bidirectional"))
      (node (ref "J9") (pin "29") (pinfunction "29_29") (pintype "bidirectional"))
    )
    (net (code "91") (name "unconnected-(D8D-C-Pad5)") (class "Default")
      (node (ref "D8") (pin "5") (pinfunction "C_5") (pintype "passive+no_connect"))
    )
    (net (code "92") (name "unconnected-(IC25-NC-Pad7)") (class "Default")
      (node (ref "IC25") (pin "7") (pinfunction "NC_7") (pintype "passive+no_connect"))
    )
    (net (code "93") (name "unconnected-(IC26-NC-Pad7)") (class "Default")
      (node (ref "IC26") (pin "7") (pinfunction "NC_7") (pintype "passive+no_connect"))
    )
    (net (code "94") (name "unconnected-(IC27C-Z-Pad9)") (class "Default")
      (node (ref "IC27") (pin "9") (pinfunction "Z_9") (pintype "bidirectional"))
    )
  )
)
